# A4_TDR_Schematic_PB.net
KiCad netlist of a schematic drawn in Altium Designer
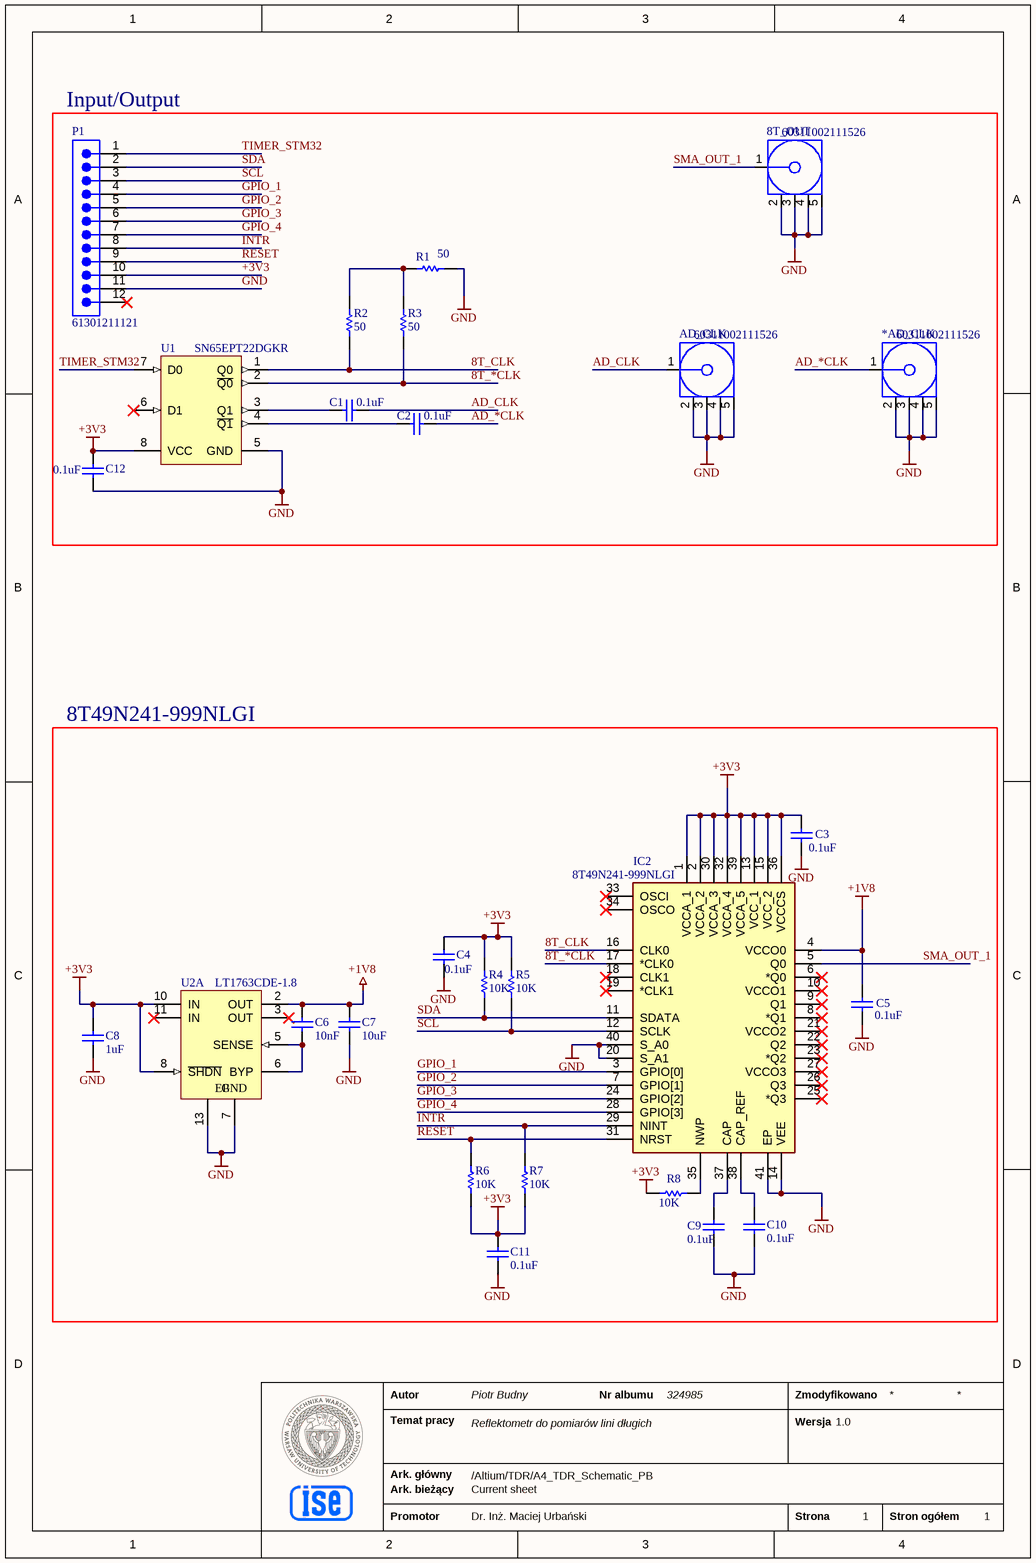
[diagram p0: A4_TDR_Schematic_PB.SchDoc]

(export (version "E")
  (design (tool "Eeschema 10.0.6"))
  (components
    (comp (ref "*AD_CLK")
      (value "60311002111526")
      (footprint "60311002111526")
      (description "60311002111526 WR-SMA_SMA PCB THT Jack_Right Angle")
      (libsource (lib "Altium Content Vault") (part "Jack_4GND"))
    )
    (comp (ref "8T_OUT")
      (value "60311002111526")
      (footprint "60311002111526")
      (description "60311002111526 WR-SMA_SMA PCB THT Jack_Right Angle")
      (libsource (lib "Altium Content Vault") (part "Jack_4GND"))
    )
    (comp (ref "AD_CLK")
      (value "60311002111526")
      (footprint "60311002111526")
      (description "60311002111526 WR-SMA_SMA PCB THT Jack_Right Angle")
      (libsource (lib "Altium Content Vault") (part "Jack_4GND"))
    )
    (comp (ref "C1")
      (value "0.1uF")
      (footprint "WCAP-CSGP_0402_L1W0.5H0.5")
      (description "CAP CER 0.1UF 10V X7R 0402")
      (fields (field (name "TOLERANCE") "10%"))
      (libsource (lib "Altium Content Vault") (part "Capacitor_Non-Polarized"))
    )
    (comp (ref "C2")
      (value "0.1uF")
      (footprint "WCAP-CSGP_0402_L1W0.5H0.5")
      (description "CAP CER 0.1UF 10V X7R 0402")
      (fields (field (name "TOLERANCE") "10%"))
      (libsource (lib "Altium Content Vault") (part "Capacitor_Non-Polarized"))
    )
    (comp (ref "C3")
      (value "0.1uF")
      (footprint "WCAP-CSGP_0402_L1W0.5H0.5")
      (description "CAP CER 0.1UF 10V X7R 0402")
      (fields (field (name "TOLERANCE") "10%"))
      (libsource (lib "Altium Content Vault") (part "Capacitor_Non-Polarized"))
    )
    (comp (ref "C4")
      (value "0.1uF")
      (footprint "WCAP-CSGP_0402_L1W0.5H0.5")
      (description "CAP CER 0.1UF 10V X7R 0402")
      (fields (field (name "TOLERANCE") "10%"))
      (libsource (lib "Altium Content Vault") (part "Capacitor_Non-Polarized"))
    )
    (comp (ref "C5")
      (value "0.1uF")
      (footprint "WCAP-CSGP_0402_L1W0.5H0.5")
      (description "CAP CER 0.1UF 10V X7R 0402")
      (fields (field (name "TOLERANCE") "10%"))
      (libsource (lib "Altium Content Vault") (part "Capacitor_Non-Polarized"))
    )
    (comp (ref "C6")
      (value "10nF")
      (footprint "WCAP-CSGP_0402_L1W0.5H0.5")
      (description "CAP CER 10000PF 10V X7R 0402")
      (fields (field (name "TOLERANCE") "10%"))
      (libsource (lib "Altium Content Vault") (part "Capacitor_Non-Polarized"))
    )
    (comp (ref "C7")
      (value "10uF")
      (footprint "WCAP-CSGP_0805_L2W1.25H1.25")
      (fields (field (name "TOLERANCE") "10%"))
      (libsource (lib "Altium Content Vault") (part "Capacitor_Non-Polarized"))
    )
    (comp (ref "C8")
      (value "1uF")
      (footprint "WCAP-CSGP_0603_L1.6W0.8H0.8_Reflow")
      (description "CAP CER 1UF 10V X7R 0603")
      (fields (field (name "TOLERANCE") "10%"))
      (libsource (lib "Altium Content Vault") (part "Capacitor_Non-Polarized"))
    )
    (comp (ref "C9")
      (value "0.1uF")
      (footprint "WCAP-CSGP_0402_L1W0.5H0.5")
      (description "CAP CER 0.1UF 10V X7R 0402")
      (fields (field (name "TOLERANCE") "10%"))
      (libsource (lib "Altium Content Vault") (part "Capacitor_Non-Polarized"))
    )
    (comp (ref "C10")
      (value "0.1uF")
      (footprint "WCAP-CSGP_0402_L1W0.5H0.5")
      (description "CAP CER 0.1UF 10V X7R 0402")
      (fields (field (name "TOLERANCE") "10%"))
      (libsource (lib "Altium Content Vault") (part "Capacitor_Non-Polarized"))
    )
    (comp (ref "C11")
      (value "0.1uF")
      (footprint "WCAP-CSGP_0402_L1W0.5H0.5")
      (description "CAP CER 0.1UF 10V X7R 0402")
      (fields (field (name "TOLERANCE") "10%"))
      (libsource (lib "Altium Content Vault") (part "Capacitor_Non-Polarized"))
    )
    (comp (ref "C12")
      (value "0.1uF")
      (footprint "WCAP-CSGP_0402_L1W0.5H0.5")
      (description "CAP CER 0.1UF 10V X7R 0402")
      (fields (field (name "TOLERANCE") "10%"))
      (libsource (lib "Altium Content Vault") (part "Capacitor_Non-Polarized"))
    )
    (comp (ref "IC2")
      (value "8T49N241-999NLGI")
      (footprint "SamacSys:QFN50P600X600X100-41N")
      (description "Integrated Circuit")
      (fields (field (name "MOUSER PART NUMBER") "972-8T49N241-999NLGI"))
      (libsource (lib "*") (part "8T49N241-999NLGI"))
    )
    (comp (ref "P1")
      (value "61301211121")
      (footprint "61301211121")
      (libsource (lib "Altium Content Vault") (part "Header_Male_1R_12P"))
    )
    (comp (ref "R1")
      (value "50")
      (footprint "RESC1005X40X25ML10T10")
      (fields (field (name "MANUFACTURER") "Multicomp") (field (name "PART NUMBER") "MC00625W0402160R4"))
      (libsource (lib "Altium Content Vault") (part "RES"))
    )
    (comp (ref "R2")
      (value "50")
      (footprint "RESC1005X40X25ML10T10")
      (fields (field (name "MANUFACTURER") "Multicomp") (field (name "PART NUMBER") "MC00625W0402160R4"))
      (libsource (lib "Altium Content Vault") (part "RES"))
    )
    (comp (ref "R3")
      (value "50")
      (footprint "RESC1005X40X25ML10T10")
      (fields (field (name "MANUFACTURER") "Multicomp") (field (name "PART NUMBER") "MC00625W0402160R4"))
      (libsource (lib "Altium Content Vault") (part "RES"))
    )
    (comp (ref "R4")
      (value "10K")
      (footprint "RESC3216X70X50LL20T25")
      (fields (field (name "MANUFACTURER") "Panasonic") (field (name "PART NUMBER") "ERA8AEB103V"))
      (libsource (lib "Altium Content Vault") (part "RES"))
    )
    (comp (ref "R5")
      (value "10K")
      (footprint "RESC3216X70X50LL20T25")
      (fields (field (name "MANUFACTURER") "Panasonic") (field (name "PART NUMBER") "ERA8AEB103V"))
      (libsource (lib "Altium Content Vault") (part "RES"))
    )
    (comp (ref "R6")
      (value "10K")
      (footprint "RESC3216X70X50LL20T25")
      (fields (field (name "MANUFACTURER") "Panasonic") (field (name "PART NUMBER") "ERA8AEB103V"))
      (libsource (lib "Altium Content Vault") (part "RES"))
    )
    (comp (ref "R7")
      (value "10K")
      (footprint "RESC3216X70X50LL20T25")
      (fields (field (name "MANUFACTURER") "Panasonic") (field (name "PART NUMBER") "ERA8AEB103V"))
      (libsource (lib "Altium Content Vault") (part "RES"))
    )
    (comp (ref "R8")
      (value "10K")
      (footprint "RESC3216X70X50LL20T25")
      (fields (field (name "MANUFACTURER") "Panasonic") (field (name "PART NUMBER") "ERA8AEB103V"))
      (libsource (lib "Altium Content Vault") (part "RES"))
    )
    (comp (ref "U1")
      (value "SN65EPT22DGKR")
      (footprint "DGK0008A_M")
      (fields (field (name "MANUFACTURER") "Texas Instruments"))
      (libsource (lib "Altium Content Vault") (part "TI-SN65EPT22-MSOP_DGK-8"))
    )
    (comp (ref "U2")
      (value "LT1763CDE-1.8")
      (footprint "LT-DE-UE-12_V")
      (fields (field (name "MANUFACTURER") "Linear Technology"))
      (libsource (lib "Altium Content Vault") (part "LT-LT1763-DE-UE-12"))
    )
  )
  (nets
    (net (code "1") (name "+1V8") (class "Default")
      (node (ref "C5") (pin "2") (pinfunction "2_2") (pintype "passive"))
      (node (ref "C6") (pin "2") (pinfunction "2_2") (pintype "passive"))
      (node (ref "C7") (pin "2") (pinfunction "2_2") (pintype "passive"))
      (node (ref "IC2") (pin "4") (pinfunction "VCCO0_4") (pintype "passive"))
      (node (ref "U2") (pin "2") (pinfunction "OUT_2") (pintype "power_in"))
    )
    (net (code "2") (name "+3V3") (class "Default")
      (node (ref "C11") (pin "2") (pinfunction "2_2") (pintype "passive"))
      (node (ref "C12") (pin "2") (pinfunction "2_2") (pintype "passive"))
      (node (ref "C3") (pin "2") (pinfunction "2_2") (pintype "passive"))
      (node (ref "C4") (pin "2") (pinfunction "2_2") (pintype "passive"))
      (node (ref "C8") (pin "2") (pinfunction "2_2") (pintype "passive"))
      (node (ref "IC2") (pin "1") (pinfunction "VCCA_1_1") (pintype "passive"))
      (node (ref "IC2") (pin "13") (pinfunction "VCC_1_13") (pintype "passive"))
      (node (ref "IC2") (pin "15") (pinfunction "VCC_2_15") (pintype "passive"))
      (node (ref "IC2") (pin "2") (pinfunction "VCCA_2_2") (pintype "passive"))
      (node (ref "IC2") (pin "30") (pinfunction "VCCA_3_30") (pintype "passive"))
      (node (ref "IC2") (pin "32") (pinfunction "VCCA_4_32") (pintype "passive"))
      (node (ref "IC2") (pin "36") (pinfunction "VCCCS_36") (pintype "passive"))
      (node (ref "IC2") (pin "39") (pinfunction "VCCA_5_39") (pintype "passive"))
      (node (ref "P1") (pin "10") (pinfunction "10_10") (pintype "passive"))
      (node (ref "R4") (pin "2") (pinfunction "2_2") (pintype "passive"))
      (node (ref "R5") (pin "2") (pinfunction "2_2") (pintype "passive"))
      (node (ref "R6") (pin "1") (pinfunction "1_1") (pintype "passive"))
      (node (ref "R7") (pin "1") (pinfunction "1_1") (pintype "passive"))
      (node (ref "R8") (pin "2") (pinfunction "2_2") (pintype "passive"))
      (node (ref "U1") (pin "8") (pinfunction "VCC_8") (pintype "power_in"))
      (node (ref "U2") (pin "10") (pinfunction "IN_10") (pintype "power_in"))
      (node (ref "U2") (pin "8") (pinfunction "~{SHDN}_8") (pintype "input"))
    )
    (net (code "3") (name "/8T_*CLK") (class "Default")
      (node (ref "IC2") (pin "17") (pinfunction "*CLK0_17") (pintype "passive"))
      (node (ref "R3") (pin "1") (pinfunction "1_1") (pintype "passive"))
      (node (ref "U1") (pin "2") (pinfunction "~{Q0}_2") (pintype "output"))
    )
    (net (code "4") (name "/8T_CLK") (class "Default")
      (node (ref "IC2") (pin "16") (pinfunction "CLK0_16") (pintype "passive"))
      (node (ref "R2") (pin "1") (pinfunction "1_1") (pintype "passive"))
      (node (ref "U1") (pin "1") (pinfunction "Q0_1") (pintype "output"))
    )
    (net (code "5") (name "/AD_*CLK") (class "Default")
      (node (ref "*AD_CLK") (pin "1") (pinfunction "Signal_1") (pintype "passive"))
      (node (ref "C2") (pin "2") (pinfunction "2_2") (pintype "passive"))
    )
    (net (code "6") (name "/AD_CLK") (class "Default")
      (node (ref "AD_CLK") (pin "1") (pinfunction "Signal_1") (pintype "passive"))
      (node (ref "C1") (pin "2") (pinfunction "2_2") (pintype "passive"))
    )
    (net (code "7") (name "/GPIO_1") (class "Default")
      (node (ref "IC2") (pin "3") (pinfunction "GPIO[0]_3") (pintype "passive"))
      (node (ref "P1") (pin "4") (pinfunction "4_4") (pintype "passive"))
    )
    (net (code "8") (name "/GPIO_2") (class "Default")
      (node (ref "IC2") (pin "7") (pinfunction "GPIO[1]_7") (pintype "passive"))
      (node (ref "P1") (pin "5") (pinfunction "5_5") (pintype "passive"))
    )
    (net (code "9") (name "/GPIO_3") (class "Default")
      (node (ref "IC2") (pin "24") (pinfunction "GPIO[2]_24") (pintype "passive"))
      (node (ref "P1") (pin "6") (pinfunction "6_6") (pintype "passive"))
    )
    (net (code "10") (name "/GPIO_4") (class "Default")
      (node (ref "IC2") (pin "28") (pinfunction "GPIO[3]_28") (pintype "passive"))
      (node (ref "P1") (pin "7") (pinfunction "7_7") (pintype "passive"))
    )
    (net (code "11") (name "/INTR") (class "Default")
      (node (ref "IC2") (pin "29") (pinfunction "NINT_29") (pintype "passive"))
      (node (ref "P1") (pin "8") (pinfunction "8_8") (pintype "passive"))
      (node (ref "R7") (pin "2") (pinfunction "2_2") (pintype "passive"))
    )
    (net (code "12") (name "/RESET") (class "Default")
      (node (ref "IC2") (pin "31") (pinfunction "NRST_31") (pintype "passive"))
      (node (ref "P1") (pin "9") (pinfunction "9_9") (pintype "passive"))
      (node (ref "R6") (pin "2") (pinfunction "2_2") (pintype "passive"))
    )
    (net (code "13") (name "/SCL") (class "Default")
      (node (ref "IC2") (pin "12") (pinfunction "SCLK_12") (pintype "passive"))
      (node (ref "P1") (pin "3") (pinfunction "3_3") (pintype "passive"))
      (node (ref "R5") (pin "1") (pinfunction "1_1") (pintype "passive"))
    )
    (net (code "14") (name "/SDA") (class "Default")
      (node (ref "IC2") (pin "11") (pinfunction "SDATA_11") (pintype "passive"))
      (node (ref "P1") (pin "2") (pinfunction "2_2") (pintype "passive"))
      (node (ref "R4") (pin "1") (pinfunction "1_1") (pintype "passive"))
    )
    (net (code "15") (name "/SMA_OUT_1") (class "Default")
      (node (ref "8T_OUT") (pin "1") (pinfunction "Signal_1") (pintype "passive"))
      (node (ref "IC2") (pin "5") (pinfunction "Q0_5") (pintype "passive"))
    )
    (net (code "16") (name "/TIMER_STM32") (class "Default")
      (node (ref "P1") (pin "1") (pinfunction "1_1") (pintype "passive"))
      (node (ref "U1") (pin "7") (pinfunction "D0_7") (pintype "input"))
    )
    (net (code "17") (name "GND") (class "Default")
      (node (ref "*AD_CLK") (pin "2") (pinfunction "GND_2") (pintype "passive"))
      (node (ref "*AD_CLK") (pin "3") (pinfunction "GND_3") (pintype "passive"))
      (node (ref "*AD_CLK") (pin "4") (pinfunction "GND_4") (pintype "passive"))
      (node (ref "*AD_CLK") (pin "5") (pinfunction "GND_5") (pintype "passive"))
      (node (ref "8T_OUT") (pin "2") (pinfunction "GND_2") (pintype "passive"))
      (node (ref "8T_OUT") (pin "3") (pinfunction "GND_3") (pintype "passive"))
      (node (ref "8T_OUT") (pin "4") (pinfunction "GND_4") (pintype "passive"))
      (node (ref "8T_OUT") (pin "5") (pinfunction "GND_5") (pintype "passive"))
      (node (ref "AD_CLK") (pin "2") (pinfunction "GND_2") (pintype "passive"))
      (node (ref "AD_CLK") (pin "3") (pinfunction "GND_3") (pintype "passive"))
      (node (ref "AD_CLK") (pin "4") (pinfunction "GND_4") (pintype "passive"))
      (node (ref "AD_CLK") (pin "5") (pinfunction "GND_5") (pintype "passive"))
      (node (ref "C10") (pin "1") (pinfunction "1_1") (pintype "passive"))
      (node (ref "C11") (pin "1") (pinfunction "1_1") (pintype "passive"))
      (node (ref "C12") (pin "1") (pinfunction "1_1") (pintype "passive"))
      (node (ref "C3") (pin "1") (pinfunction "1_1") (pintype "passive"))
      (node (ref "C4") (pin "1") (pinfunction "1_1") (pintype "passive"))
      (node (ref "C5") (pin "1") (pinfunction "1_1") (pintype "passive"))
      (node (ref "C7") (pin "1") (pinfunction "1_1") (pintype "passive"))
      (node (ref "C8") (pin "1") (pinfunction "1_1") (pintype "passive"))
      (node (ref "C9") (pin "1") (pinfunction "1_1") (pintype "passive"))
      (node (ref "IC2") (pin "14") (pinfunction "VEE_14") (pintype "passive"))
      (node (ref "IC2") (pin "20") (pinfunction "S_A1_20") (pintype "passive"))
      (node (ref "IC2") (pin "40") (pinfunction "S_A0_40") (pintype "passive"))
      (node (ref "IC2") (pin "41") (pinfunction "EP_41") (pintype "passive"))
      (node (ref "P1") (pin "11") (pinfunction "11_11") (pintype "passive"))
      (node (ref "R1") (pin "2") (pinfunction "2_2") (pintype "passive"))
      (node (ref "U1") (pin "5") (pinfunction "GND_5") (pintype "power_in"))
      (node (ref "U2") (pin "13") (pinfunction "EP_13") (pintype "power_in"))
      (node (ref "U2") (pin "7") (pinfunction "GND_7") (pintype "power_in"))
    )
    (net (code "18") (name "Net-(IC2-CAP)") (class "Default")
      (node (ref "C9") (pin "2") (pinfunction "2_2") (pintype "passive"))
      (node (ref "IC2") (pin "37") (pinfunction "CAP_37") (pintype "passive"))
    )
    (net (code "19") (name "Net-(IC2-CAP_REF)") (class "Default")
      (node (ref "C10") (pin "2") (pinfunction "2_2") (pintype "passive"))
      (node (ref "IC2") (pin "38") (pinfunction "CAP_REF_38") (pintype "passive"))
    )
    (net (code "20") (name "Net-(IC2-NWP)") (class "Default")
      (node (ref "IC2") (pin "35") (pinfunction "NWP_35") (pintype "passive"))
      (node (ref "R8") (pin "1") (pinfunction "1_1") (pintype "passive"))
    )
    (net (code "21") (name "Net-(R1-Pad1)") (class "Default")
      (node (ref "R1") (pin "1") (pinfunction "1_1") (pintype "passive"))
      (node (ref "R2") (pin "2") (pinfunction "2_2") (pintype "passive"))
      (node (ref "R3") (pin "2") (pinfunction "2_2") (pintype "passive"))
    )
    (net (code "22") (name "Net-(U1-Q1)") (class "Default")
      (node (ref "C1") (pin "1") (pinfunction "1_1") (pintype "passive"))
      (node (ref "U1") (pin "3") (pinfunction "Q1_3") (pintype "output"))
    )
    (net (code "23") (name "Net-(U1-~{Q1})") (class "Default")
      (node (ref "C2") (pin "1") (pinfunction "1_1") (pintype "passive"))
      (node (ref "U1") (pin "4") (pinfunction "~{Q1}_4") (pintype "output"))
    )
    (net (code "24") (name "Net-(U2A-BYP)") (class "Default")
      (node (ref "C6") (pin "1") (pinfunction "1_1") (pintype "passive"))
      (node (ref "U2") (pin "5") (pinfunction "SENSE_5") (pintype "input"))
      (node (ref "U2") (pin "6") (pinfunction "BYP_6") (pintype "passive"))
    )
    (net (code "25") (name "unconnected-(IC2-*CLK1-Pad19)") (class "Default")
      (node (ref "IC2") (pin "19") (pinfunction "*CLK1_19") (pintype "passive+no_connect"))
    )
    (net (code "26") (name "unconnected-(IC2-*Q0-Pad6)") (class "Default")
      (node (ref "IC2") (pin "6") (pinfunction "*Q0_6") (pintype "passive+no_connect"))
    )
    (net (code "27") (name "unconnected-(IC2-*Q1-Pad8)") (class "Default")
      (node (ref "IC2") (pin "8") (pinfunction "*Q1_8") (pintype "passive+no_connect"))
    )
    (net (code "28") (name "unconnected-(IC2-*Q2-Pad23)") (class "Default")
      (node (ref "IC2") (pin "23") (pinfunction "*Q2_23") (pintype "passive+no_connect"))
    )
    (net (code "29") (name "unconnected-(IC2-*Q3-Pad25)") (class "Default")
      (node (ref "IC2") (pin "25") (pinfunction "*Q3_25") (pintype "passive+no_connect"))
    )
    (net (code "30") (name "unconnected-(IC2-CLK1-Pad18)") (class "Default")
      (node (ref "IC2") (pin "18") (pinfunction "CLK1_18") (pintype "passive+no_connect"))
    )
    (net (code "31") (name "unconnected-(IC2-OSCI-Pad33)") (class "Default")
      (node (ref "IC2") (pin "33") (pinfunction "OSCI_33") (pintype "passive+no_connect"))
    )
    (net (code "32") (name "unconnected-(IC2-OSCO-Pad34)") (class "Default")
      (node (ref "IC2") (pin "34") (pinfunction "OSCO_34") (pintype "passive+no_connect"))
    )
    (net (code "33") (name "unconnected-(IC2-Q1-Pad9)") (class "Default")
      (node (ref "IC2") (pin "9") (pinfunction "Q1_9") (pintype "passive+no_connect"))
    )
    (net (code "34") (name "unconnected-(IC2-Q2-Pad22)") (class "Default")
      (node (ref "IC2") (pin "22") (pinfunction "Q2_22") (pintype "passive+no_connect"))
    )
    (net (code "35") (name "unconnected-(IC2-Q3-Pad26)") (class "Default")
      (node (ref "IC2") (pin "26") (pinfunction "Q3_26") (pintype "passive+no_connect"))
    )
    (net (code "36") (name "unconnected-(IC2-VCCO1-Pad10)") (class "Default")
      (node (ref "IC2") (pin "10") (pinfunction "VCCO1_10") (pintype "passive+no_connect"))
    )
    (net (code "37") (name "unconnected-(IC2-VCCO2-Pad21)") (class "Default")
      (node (ref "IC2") (pin "21") (pinfunction "VCCO2_21") (pintype "passive+no_connect"))
    )
    (net (code "38") (name "unconnected-(IC2-VCCO3-Pad27)") (class "Default")
      (node (ref "IC2") (pin "27") (pinfunction "VCCO3_27") (pintype "passive+no_connect"))
    )
    (net (code "39") (name "unconnected-(P1-Pad12)") (class "Default")
      (node (ref "P1") (pin "12") (pinfunction "12_12") (pintype "passive+no_connect"))
    )
    (net (code "40") (name "unconnected-(U1-D1-Pad6)") (class "Default")
      (node (ref "U1") (pin "6") (pinfunction "D1_6") (pintype "input+no_connect"))
    )
    (net (code "41") (name "unconnected-(U2A-IN-Pad11)") (class "Default")
      (node (ref "U2") (pin "11") (pinfunction "IN_11") (pintype "power_in+no_connect"))
    )
    (net (code "42") (name "unconnected-(U2A-OUT-Pad3)") (class "Default")
      (node (ref "U2") (pin "3") (pinfunction "OUT_3") (pintype "power_in+no_connect"))
    )
  )
)
